# Dimming.net
KiCad netlist of a schematic drawn in Altium Designer
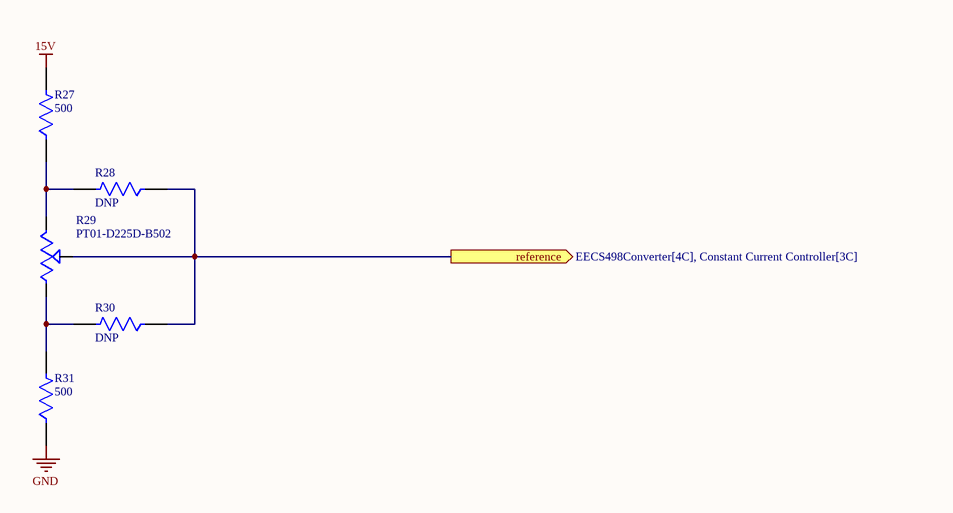
[diagram p0: Dimming.SchDoc]

(export (version "E")
  (design (tool "Eeschema 10.0.6"))
  (components
    (comp (ref "R27")
      (value "500")
      (footprint "FP-RLR07-MFG")
      (description "Resistor, ± 1%, 250 mW, Axial Leaded, Metal Film, Military Reliability")
      (fields (field (name "TOLERANCE") "1%"))
      (libsource (lib "EECS498Converter") (part "Resistor"))
    )
    (comp (ref "R28")
      (value "DNP")
      (footprint "FP-RLR07-MFG")
      (description "Resistor, ± 1%, 250 mW, Axial Leaded, Metal Film, Military Reliability")
      (fields (field (name "TOLERANCE") "1%"))
      (libsource (lib "EECS498Converter") (part "Resistor"))
    )
    (comp (ref "R29")
      (value "PT01-D225D-B502")
      (footprint "TRIM_PT01-D225D-B502")
      (libsource (lib "EECS498Converter") (part "PT01-D225D-B502"))
    )
    (comp (ref "R30")
      (value "DNP")
      (footprint "FP-RLR07-MFG")
      (description "Resistor, ± 1%, 250 mW, Axial Leaded, Metal Film, Military Reliability")
      (fields (field (name "TOLERANCE") "1%"))
      (libsource (lib "EECS498Converter") (part "Resistor"))
    )
    (comp (ref "R31")
      (value "500")
      (footprint "FP-RLR07-MFG")
      (description "Resistor, ± 1%, 250 mW, Axial Leaded, Metal Film, Military Reliability")
      (fields (field (name "TOLERANCE") "1%"))
      (libsource (lib "EECS498Converter") (part "Resistor"))
    )
  )
  (nets
    (net (code "1") (name "/reference") (class "Default")
      (node (ref "R28") (pin "1") (pinfunction "1_1") (pintype "passive"))
      (node (ref "R29") (pin "2") (pinfunction "2_2") (pintype "passive"))
      (node (ref "R30") (pin "1") (pinfunction "1_1") (pintype "passive"))
    )
    (net (code "2") (name "15V") (class "Default")
      (node (ref "R27") (pin "2") (pinfunction "2_2") (pintype "passive"))
    )
    (net (code "3") (name "GND") (class "Default")
      (node (ref "R31") (pin "1") (pinfunction "1_1") (pintype "passive"))
    )
    (net (code "4") (name "Net-(R27-Pad1)") (class "Default")
      (node (ref "R27") (pin "1") (pinfunction "1_1") (pintype "passive"))
      (node (ref "R28") (pin "2") (pinfunction "2_2") (pintype "passive"))
      (node (ref "R29") (pin "1") (pinfunction "1_1") (pintype "passive"))
    )
    (net (code "5") (name "Net-(R29-Pad3)") (class "Default")
      (node (ref "R29") (pin "3") (pinfunction "3_3") (pintype "passive"))
      (node (ref "R30") (pin "2") (pinfunction "2_2") (pintype "passive"))
      (node (ref "R31") (pin "2") (pinfunction "2_2") (pintype "passive"))
    )
  )
)
